# MinieasySens-RS485_V01-Build009.net
KiCad netlist of a schematic drawn in EAGLE
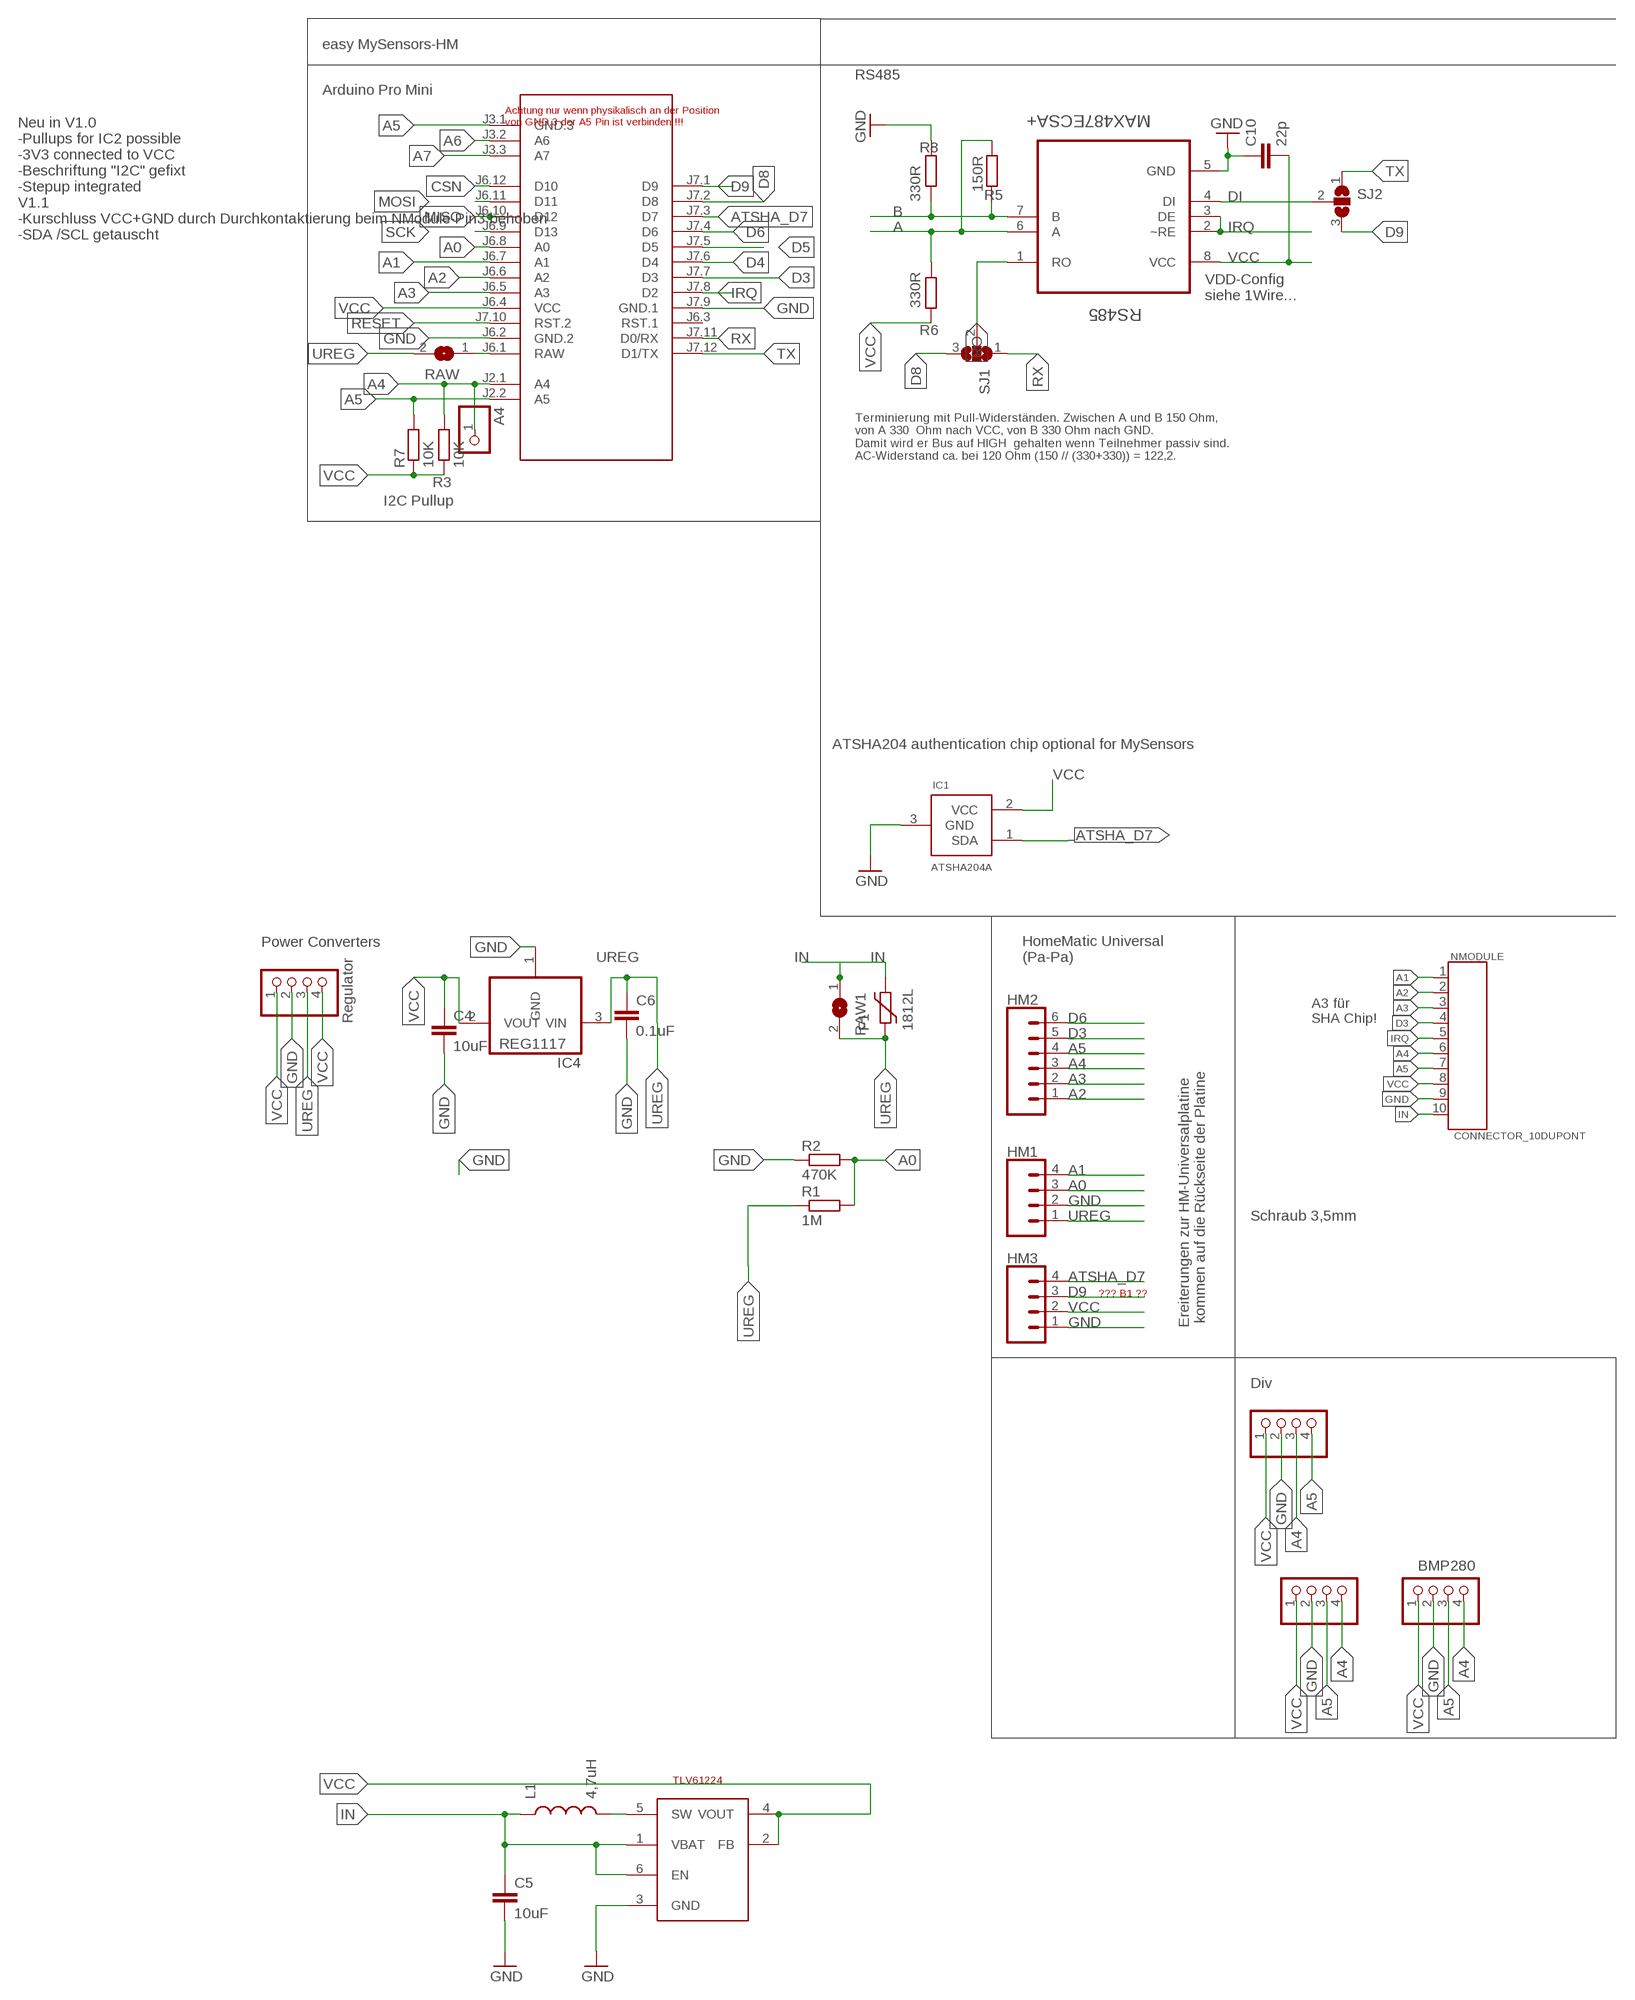
[diagram p0: schematic, sheet 1, part 1 of 2]
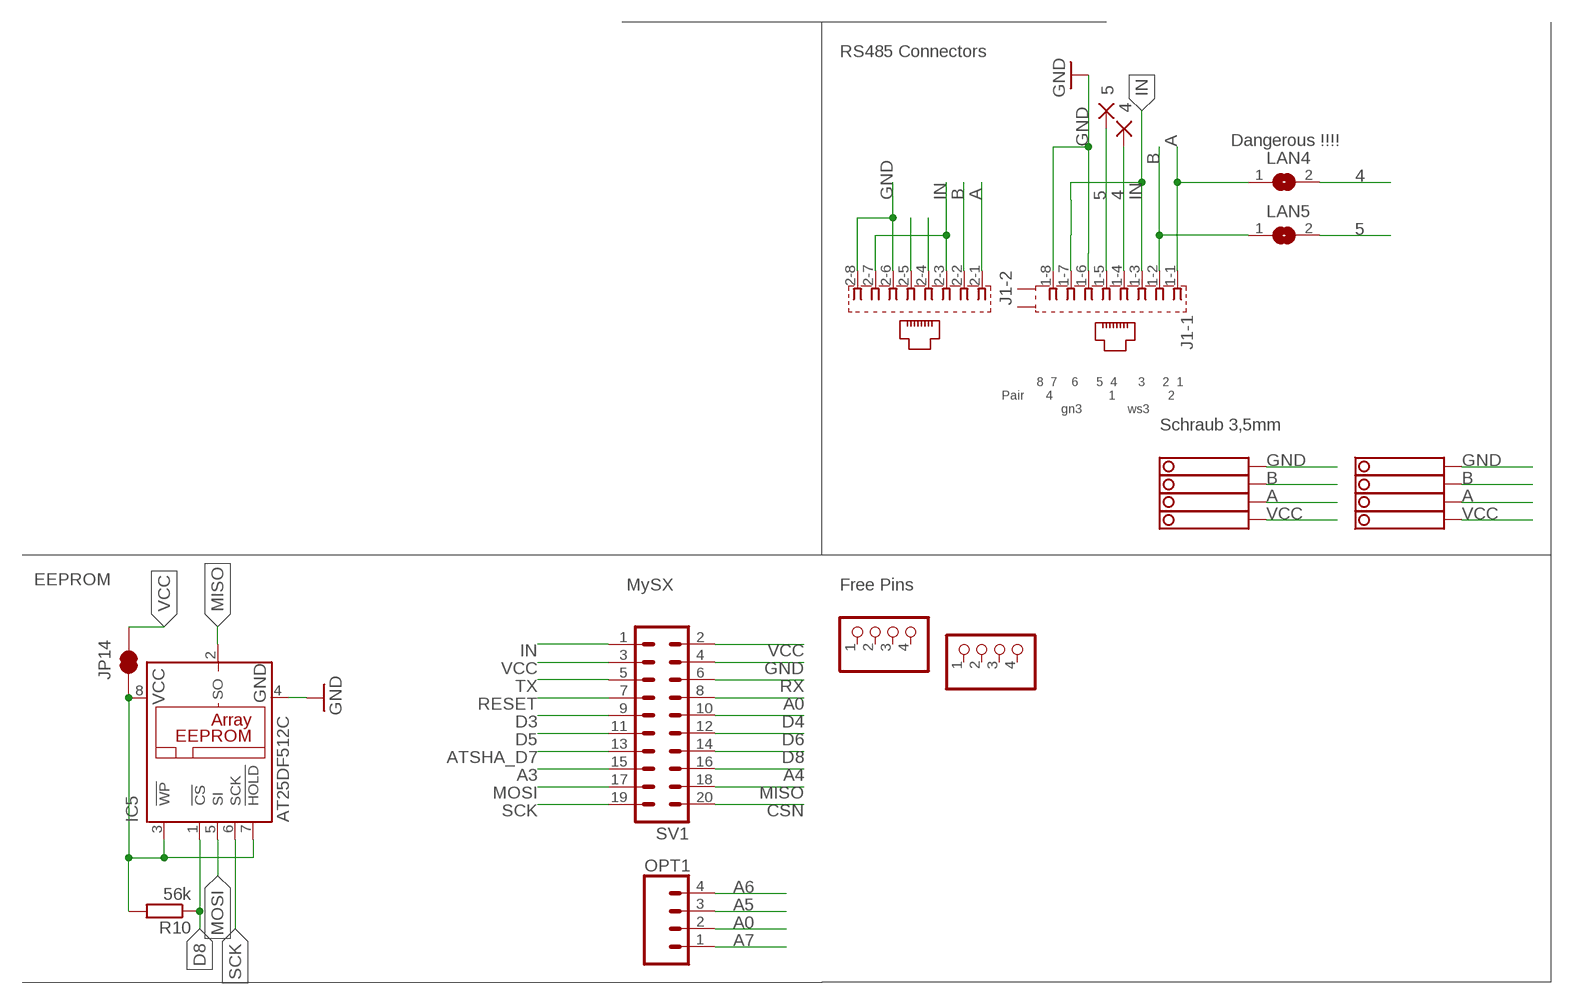
[diagram p1: schematic, sheet 1, part 2 of 2]

(export (version "E")
  (design (tool "Eeschema 10.0.6"))
  (components
    (comp (ref "4")
      (value "1,6/0,8")
      (footprint "eagle-import:1,6_0,8")
      (libsource (lib "eagle-import") (part "1,6/0,8"))
    )
    (comp (ref "5")
      (value "1,6/0,8")
      (footprint "eagle-import:1,6_0,8")
      (libsource (lib "eagle-import") (part "1,6/0,8"))
    )
    (comp (ref "A4")
      (value "PINHD-1X1")
      (footprint "eagle-import:1X01")
      (libsource (lib "eagle-import") (part "PINHD-1X1"))
    )
    (comp (ref "BH1750")
      (value "PINHD-1X04_2.54-S")
      (footprint "eagle-import:1X04-S")
      (libsource (lib "eagle-import") (part "PINHD-1X04_2.54-S"))
    )
    (comp (ref "C4")
      (value "10uF")
      (footprint "eagle-import:C1210")
      (libsource (lib "eagle-import") (part "C-EUC1210"))
    )
    (comp (ref "C5")
      (value "10uF")
      (footprint "eagle-import:0805")
      (libsource (lib "eagle-import") (part "CAP0805"))
    )
    (comp (ref "C6")
      (value "0.1uF")
      (footprint "eagle-import:C1206")
      (libsource (lib "eagle-import") (part "C-EUC1206"))
    )
    (comp (ref "C10")
      (value "22p")
      (footprint "eagle-import:C0805")
      (libsource (lib "eagle-import") (part "C-EUC0805"))
    )
    (comp (ref "F1")
      (value "1812L")
      (footprint "eagle-import:1812L")
      (libsource (lib "eagle-import") (part "1812L"))
    )
    (comp (ref "HM1")
      (value "CONN_04")
      (footprint "eagle-import:1X04")
      (libsource (lib "eagle-import") (part "CONN_04"))
    )
    (comp (ref "HM2")
      (value "CONN_06SILK_FEMALE_PTH")
      (footprint "eagle-import:1X06")
      (libsource (lib "eagle-import") (part "CONN_06SILK_FEMALE_PTH"))
    )
    (comp (ref "HM3")
      (value "CONN_04")
      (footprint "eagle-import:1X04")
      (libsource (lib "eagle-import") (part "CONN_04"))
    )
    (comp (ref "I2C-1")
      (value "PINHD-1X04_2.54-S")
      (footprint "eagle-import:1X04-S")
      (libsource (lib "eagle-import") (part "PINHD-1X04_2.54-S"))
    )
    (comp (ref "I2C-2")
      (value "PINHD-1X04_2.54-S")
      (footprint "eagle-import:1X04-S")
      (libsource (lib "eagle-import") (part "PINHD-1X04_2.54-S"))
    )
    (comp (ref "IC1")
      (value "ATSHA204A")
      (footprint "eagle-import:SOT23")
      (libsource (lib "eagle-import") (part "ATSHA204A"))
    )
    (comp (ref "IC4")
      (value "REG1117")
      (footprint "eagle-import:SOT223")
      (libsource (lib "eagle-import") (part "REG1117"))
    )
    (comp (ref "IC5")
      (value "AT25DF512C")
      (footprint "eagle-import:SO-08")
      (fields (field (name "MF") "MICROCHIP") (field (name "MPN") "25AA080/SN"))
      (libsource (lib "eagle-import") (part "25SNAA080"))
    )
    (comp (ref "J1")
      (value "557570-1")
      (footprint "eagle-import:557570-1")
      (libsource (lib "eagle-import") (part "557570-1"))
    )
    (comp (ref "JP2")
      (value "PINHD-1X04_2.54-S")
      (footprint "eagle-import:1X04-S")
      (libsource (lib "eagle-import") (part "PINHD-1X04_2.54-S"))
    )
    (comp (ref "JP4")
      (value "PINHD-1X04_2.54-S")
      (footprint "eagle-import:1X04-S")
      (libsource (lib "eagle-import") (part "PINHD-1X04_2.54-S"))
    )
    (comp (ref "JP14")
      (value "JUMPER-SMT_2_NC_TRACE_SILK")
      (footprint "eagle-import:SMT-JUMPER_2_NC_TRACE_SILK")
      (libsource (lib "eagle-import") (part "JUMPER-SMT_2_NC_TRACE_SILK"))
    )
    (comp (ref "L1")
      (value "4,7uH")
      (footprint "eagle-import:0805")
      (libsource (lib "eagle-import") (part "INDUCTOR0805"))
    )
    (comp (ref "LAN4")
      (value "SJ")
      (footprint "eagle-import:SJ")
      (libsource (lib "eagle-import") (part "SJ"))
    )
    (comp (ref "LAN5")
      (value "SJ")
      (footprint "eagle-import:SJ")
      (libsource (lib "eagle-import") (part "SJ"))
    )
    (comp (ref "M1")
      (value "ARDUINO-PRO-MINI-3.3V#NP")
      (footprint "eagle-import:ARDUINO-PRO-MINI#NP")
      (libsource (lib "eagle-import") (part "ARDUINO-PRO-MINI-#NP3.3V"))
    )
    (comp (ref "NMODULE")
      (value "CONNECTOR_10DUPONT")
      (footprint "eagle-import:DUPONT_10")
      (libsource (lib "eagle-import") (part "CONNECTOR_10DUPONT"))
    )
    (comp (ref "OPT1")
      (value "CONN_04")
      (footprint "eagle-import:1X04")
      (libsource (lib "eagle-import") (part "CONN_04"))
    )
    (comp (ref "R1")
      (value "1M")
      (footprint "eagle-import:R0805")
      (libsource (lib "eagle-import") (part "R-EU_R0805"))
    )
    (comp (ref "R2")
      (value "470K")
      (footprint "eagle-import:R0805")
      (libsource (lib "eagle-import") (part "R-EU_R0805"))
    )
    (comp (ref "R3")
      (value "10K")
      (footprint "eagle-import:R0805")
      (libsource (lib "eagle-import") (part "R-EU_R0805"))
    )
    (comp (ref "R5")
      (value "150R")
      (footprint "eagle-import:R0805")
      (libsource (lib "eagle-import") (part "R-EU_R0805"))
    )
    (comp (ref "R6")
      (value "330R")
      (footprint "eagle-import:R0805")
      (libsource (lib "eagle-import") (part "R-EU_R0805"))
    )
    (comp (ref "R7")
      (value "10K")
      (footprint "eagle-import:R0805")
      (libsource (lib "eagle-import") (part "R-EU_R0805"))
    )
    (comp (ref "R8")
      (value "330R")
      (footprint "eagle-import:R0805")
      (libsource (lib "eagle-import") (part "R-EU_R0805"))
    )
    (comp (ref "R10")
      (value "56k")
      (footprint "eagle-import:M0805")
      (libsource (lib "eagle-import") (part "resistor_R-EU_M0805"))
    )
    (comp (ref "RAW") (value "SJ") (footprint "eagle-import:SJ") (libsource (lib "eagle-import") (part "SJ")))
    (comp (ref "RAW1")
      (value "SJ")
      (footprint "eagle-import:SJ")
      (libsource (lib "eagle-import") (part "SJ"))
    )
    (comp (ref "RS485")
      (value "MAX487ECSA+")
      (footprint "eagle-import:SOIC127P600X175-8N")
      (libsource (lib "eagle-import") (part "MAX487ECSA+"))
    )
    (comp (ref "SJ1")
      (value "SJ2W")
      (footprint "eagle-import:SJ_2")
      (libsource (lib "eagle-import") (part "SJ2W"))
    )
    (comp (ref "SJ2")
      (value "SJ2W")
      (footprint "eagle-import:SJ_2")
      (libsource (lib "eagle-import") (part "SJ2W"))
    )
    (comp (ref "STEPDWN")
      (value "PINHD-1X04_2.54-S")
      (footprint "eagle-import:1X04-S")
      (libsource (lib "eagle-import") (part "PINHD-1X04_2.54-S"))
    )
    (comp (ref "STEPUP")
      (value "TLV61224")
      (footprint "eagle-import:SOT23-6L")
      (libsource (lib "eagle-import") (part "TI-TLV61224"))
    )
    (comp (ref "SV1")
      (value "MA10-2")
      (footprint "eagle-import:MA10-2")
      (libsource (lib "eagle-import") (part "MA10-2"))
    )
    (comp (ref "X1")
      (value "1751264")
      (footprint "eagle-import:1751264")
      (libsource (lib "eagle-import") (part "1751264"))
    )
    (comp (ref "X4")
      (value "1751264")
      (footprint "eagle-import:1751264")
      (libsource (lib "eagle-import") (part "1751264"))
    )
  )
  (nets
    (net (code "1") (name "/4") (class "Default")
      (node (ref "4") (pin "1") (pinfunction "P_1") (pintype "passive"))
      (node (ref "J1") (pin "1-4") (pinfunction "4_1-4") (pintype "passive"))
      (node (ref "LAN4") (pin "2") (pinfunction "2_2") (pintype "passive"))
    )
    (net (code "2") (name "/5") (class "Default")
      (node (ref "5") (pin "1") (pinfunction "P_1") (pintype "passive"))
      (node (ref "J1") (pin "1-5") (pinfunction "5_1-5") (pintype "passive"))
      (node (ref "LAN5") (pin "2") (pinfunction "2_2") (pintype "passive"))
    )
    (net (code "3") (name "/A") (class "Default")
      (node (ref "J1") (pin "1-1") (pinfunction "1_1-1") (pintype "passive"))
      (node (ref "J1") (pin "2-1") (pinfunction "1_2-1") (pintype "passive"))
      (node (ref "LAN4") (pin "1") (pinfunction "1_1") (pintype "passive"))
      (node (ref "R5") (pin "1") (pinfunction "1_1") (pintype "passive"))
      (node (ref "R6") (pin "2") (pinfunction "2_2") (pintype "passive"))
      (node (ref "RS485") (pin "6") (pinfunction "A_6") (pintype "bidirectional"))
      (node (ref "X1") (pin "2") (pinfunction "K_2") (pintype "passive"))
      (node (ref "X4") (pin "2") (pinfunction "K_2") (pintype "passive"))
    )
    (net (code "4") (name "/B") (class "Default")
      (node (ref "J1") (pin "1-2") (pinfunction "2_1-2") (pintype "passive"))
      (node (ref "J1") (pin "2-2") (pinfunction "2_2-2") (pintype "passive"))
      (node (ref "LAN5") (pin "1") (pinfunction "1_1") (pintype "passive"))
      (node (ref "R5") (pin "2") (pinfunction "2_2") (pintype "passive"))
      (node (ref "R8") (pin "1") (pinfunction "1_1") (pintype "passive"))
      (node (ref "RS485") (pin "7") (pinfunction "B_7") (pintype "bidirectional"))
      (node (ref "X1") (pin "3") (pinfunction "K_3") (pintype "passive"))
      (node (ref "X4") (pin "3") (pinfunction "K_3") (pintype "passive"))
    )
    (net (code "5") (name "/DI") (class "Default")
      (node (ref "RS485") (pin "4") (pinfunction "DI_4") (pintype "input"))
      (node (ref "SJ2") (pin "2") (pinfunction "2_2") (pintype "passive"))
    )
    (net (code "6") (name "A0") (class "Default")
      (node (ref "HM1") (pin "3") (pinfunction "3_3") (pintype "passive"))
      (node (ref "M1") (pin "J6.8") (pinfunction "A0_J6.8") (pintype "bidirectional"))
      (node (ref "OPT1") (pin "2") (pinfunction "2_2") (pintype "passive"))
      (node (ref "R1") (pin "2") (pinfunction "2_2") (pintype "passive"))
      (node (ref "R2") (pin "2") (pinfunction "2_2") (pintype "passive"))
      (node (ref "SV1") (pin "8") (pinfunction "8_8") (pintype "passive"))
    )
    (net (code "7") (name "A1") (class "Default")
      (node (ref "HM1") (pin "4") (pinfunction "4_4") (pintype "passive"))
      (node (ref "M1") (pin "J6.7") (pinfunction "A1_J6.7") (pintype "bidirectional"))
      (node (ref "NMODULE") (pin "1") (pinfunction "1_1") (pintype "bidirectional"))
    )
    (net (code "8") (name "A2") (class "Default")
      (node (ref "HM2") (pin "1") (pinfunction "1_1") (pintype "passive"))
      (node (ref "M1") (pin "J6.6") (pinfunction "A2_J6.6") (pintype "bidirectional"))
      (node (ref "NMODULE") (pin "2") (pinfunction "2_2") (pintype "bidirectional"))
    )
    (net (code "9") (name "A3") (class "Default")
      (node (ref "HM2") (pin "2") (pinfunction "2_2") (pintype "passive"))
      (node (ref "M1") (pin "J6.5") (pinfunction "A3_J6.5") (pintype "bidirectional"))
      (node (ref "NMODULE") (pin "3") (pinfunction "3_3") (pintype "bidirectional"))
      (node (ref "SV1") (pin "15") (pinfunction "15_15") (pintype "passive"))
    )
    (net (code "10") (name "A4") (class "Default")
      (node (ref "A4") (pin "1") (pinfunction "1_1") (pintype "passive"))
      (node (ref "BH1750") (pin "4") (pinfunction "4_4") (pintype "passive"))
      (node (ref "HM2") (pin "3") (pinfunction "3_3") (pintype "passive"))
      (node (ref "I2C-1") (pin "4") (pinfunction "4_4") (pintype "passive"))
      (node (ref "I2C-2") (pin "3") (pinfunction "3_3") (pintype "passive"))
      (node (ref "M1") (pin "J2.1") (pinfunction "A4_J2.1") (pintype "bidirectional"))
      (node (ref "NMODULE") (pin "6") (pinfunction "6_6") (pintype "bidirectional"))
      (node (ref "R3") (pin "2") (pinfunction "2_2") (pintype "passive"))
      (node (ref "SV1") (pin "16") (pinfunction "16_16") (pintype "passive"))
    )
    (net (code "11") (name "A5") (class "Default")
      (node (ref "BH1750") (pin "3") (pinfunction "3_3") (pintype "passive"))
      (node (ref "HM2") (pin "4") (pinfunction "4_4") (pintype "passive"))
      (node (ref "I2C-1") (pin "3") (pinfunction "3_3") (pintype "passive"))
      (node (ref "I2C-2") (pin "4") (pinfunction "4_4") (pintype "passive"))
      (node (ref "M1") (pin "J2.2") (pinfunction "A5_J2.2") (pintype "bidirectional"))
      (node (ref "M1") (pin "J3.1") (pinfunction "GND.3_J3.1") (pintype "bidirectional"))
      (node (ref "NMODULE") (pin "7") (pinfunction "7_7") (pintype "bidirectional"))
      (node (ref "OPT1") (pin "3") (pinfunction "3_3") (pintype "passive"))
      (node (ref "R7") (pin "2") (pinfunction "2_2") (pintype "passive"))
    )
    (net (code "12") (name "A6") (class "Default")
      (node (ref "M1") (pin "J3.2") (pinfunction "A6_J3.2") (pintype "bidirectional"))
      (node (ref "OPT1") (pin "4") (pinfunction "4_4") (pintype "passive"))
    )
    (net (code "13") (name "A7") (class "Default")
      (node (ref "M1") (pin "J3.3") (pinfunction "A7_J3.3") (pintype "bidirectional"))
      (node (ref "OPT1") (pin "1") (pinfunction "1_1") (pintype "passive"))
    )
    (net (code "14") (name "ATSHA_D7") (class "Default")
      (node (ref "HM3") (pin "4") (pinfunction "4_4") (pintype "passive"))
      (node (ref "IC1") (pin "1") (pinfunction "SDA_1") (pintype "bidirectional"))
      (node (ref "M1") (pin "J7.3") (pinfunction "D7_J7.3") (pintype "bidirectional"))
      (node (ref "SV1") (pin "13") (pinfunction "13_13") (pintype "passive"))
    )
    (net (code "15") (name "CSN") (class "Default")
      (node (ref "M1") (pin "J6.12") (pinfunction "D10_J6.12") (pintype "bidirectional"))
      (node (ref "SV1") (pin "20") (pinfunction "20_20") (pintype "passive"))
    )
    (net (code "16") (name "D3") (class "Default")
      (node (ref "HM2") (pin "5") (pinfunction "5_5") (pintype "passive"))
      (node (ref "M1") (pin "J7.7") (pinfunction "D3_J7.7") (pintype "bidirectional"))
      (node (ref "NMODULE") (pin "4") (pinfunction "4_4") (pintype "bidirectional"))
      (node (ref "SV1") (pin "9") (pinfunction "9_9") (pintype "passive"))
    )
    (net (code "17") (name "D4") (class "Default")
      (node (ref "M1") (pin "J7.6") (pinfunction "D4_J7.6") (pintype "bidirectional"))
      (node (ref "SV1") (pin "10") (pinfunction "10_10") (pintype "passive"))
    )
    (net (code "18") (name "D5") (class "Default")
      (node (ref "M1") (pin "J7.5") (pinfunction "D5_J7.5") (pintype "bidirectional"))
      (node (ref "SV1") (pin "11") (pinfunction "11_11") (pintype "passive"))
    )
    (net (code "19") (name "D6") (class "Default")
      (node (ref "HM2") (pin "6") (pinfunction "6_6") (pintype "passive"))
      (node (ref "M1") (pin "J7.4") (pinfunction "D6_J7.4") (pintype "bidirectional"))
      (node (ref "SV1") (pin "12") (pinfunction "12_12") (pintype "passive"))
    )
    (net (code "20") (name "D8") (class "Default")
      (node (ref "IC5") (pin "1") (pinfunction "~{CS}_1") (pintype "input"))
      (node (ref "M1") (pin "J7.2") (pinfunction "D8_J7.2") (pintype "bidirectional"))
      (node (ref "R10") (pin "1") (pinfunction "1_1") (pintype "passive"))
      (node (ref "SJ1") (pin "3") (pinfunction "3_3") (pintype "passive"))
      (node (ref "SV1") (pin "14") (pinfunction "14_14") (pintype "passive"))
    )
    (net (code "21") (name "D9") (class "Default")
      (node (ref "HM3") (pin "3") (pinfunction "3_3") (pintype "passive"))
      (node (ref "M1") (pin "J7.1") (pinfunction "D9_J7.1") (pintype "bidirectional"))
      (node (ref "SJ2") (pin "3") (pinfunction "3_3") (pintype "passive"))
    )
    (net (code "22") (name "GND") (class "Default")
      (node (ref "BH1750") (pin "2") (pinfunction "2_2") (pintype "passive"))
      (node (ref "C10") (pin "1") (pinfunction "1_1") (pintype "passive"))
      (node (ref "C4") (pin "2") (pinfunction "2_2") (pintype "passive"))
      (node (ref "C5") (pin "2") (pinfunction "2_2") (pintype "passive"))
      (node (ref "C6") (pin "2") (pinfunction "2_2") (pintype "passive"))
      (node (ref "HM1") (pin "2") (pinfunction "2_2") (pintype "passive"))
      (node (ref "HM3") (pin "1") (pinfunction "1_1") (pintype "passive"))
      (node (ref "I2C-1") (pin "2") (pinfunction "2_2") (pintype "passive"))
      (node (ref "I2C-2") (pin "2") (pinfunction "2_2") (pintype "passive"))
      (node (ref "IC1") (pin "3") (pinfunction "GND_3") (pintype "bidirectional"))
      (node (ref "IC4") (pin "1") (pinfunction "GND_1") (pintype "power_in"))
      (node (ref "IC5") (pin "4") (pinfunction "GND_4") (pintype "power_in"))
      (node (ref "J1") (pin "1-6") (pinfunction "6_1-6") (pintype "passive"))
      (node (ref "J1") (pin "1-8") (pinfunction "8_1-8") (pintype "passive"))
      (node (ref "J1") (pin "2-6") (pinfunction "6_2-6") (pintype "passive"))
      (node (ref "J1") (pin "2-8") (pinfunction "8_2-8") (pintype "passive"))
      (node (ref "M1") (pin "J6.2") (pinfunction "GND.2_J6.2") (pintype "power_in"))
      (node (ref "M1") (pin "J7.9") (pinfunction "GND.1_J7.9") (pintype "power_in"))
      (node (ref "NMODULE") (pin "9") (pinfunction "9_9") (pintype "bidirectional"))
      (node (ref "R2") (pin "1") (pinfunction "1_1") (pintype "passive"))
      (node (ref "R8") (pin "2") (pinfunction "2_2") (pintype "passive"))
      (node (ref "RS485") (pin "5") (pinfunction "GND_5") (pintype "passive"))
      (node (ref "STEPDWN") (pin "2") (pinfunction "2_2") (pintype "passive"))
      (node (ref "STEPUP") (pin "3") (pinfunction "GND_3") (pintype "power_in"))
      (node (ref "SV1") (pin "4") (pinfunction "4_4") (pintype "passive"))
      (node (ref "X1") (pin "4") (pinfunction "K_4") (pintype "passive"))
      (node (ref "X4") (pin "4") (pinfunction "K_4") (pintype "passive"))
    )
    (net (code "23") (name "IN") (class "Default")
      (node (ref "C5") (pin "1") (pinfunction "1_1") (pintype "passive"))
      (node (ref "F1") (pin "P$2") (pinfunction "2_P$2") (pintype "passive"))
      (node (ref "J1") (pin "1-3") (pinfunction "3_1-3") (pintype "passive"))
      (node (ref "J1") (pin "1-7") (pinfunction "7_1-7") (pintype "passive"))
      (node (ref "J1") (pin "2-3") (pinfunction "3_2-3") (pintype "passive"))
      (node (ref "J1") (pin "2-7") (pinfunction "7_2-7") (pintype "passive"))
      (node (ref "L1") (pin "1") (pinfunction "1_1") (pintype "passive"))
      (node (ref "NMODULE") (pin "10") (pinfunction "10_10") (pintype "bidirectional"))
      (node (ref "RAW1") (pin "1") (pinfunction "1_1") (pintype "passive"))
      (node (ref "STEPUP") (pin "1") (pinfunction "VBAT_1") (pintype "power_in"))
      (node (ref "STEPUP") (pin "6") (pinfunction "EN_6") (pintype "input"))
      (node (ref "SV1") (pin "1") (pinfunction "1_1") (pintype "passive"))
    )
    (net (code "24") (name "IRQ") (class "Default")
      (node (ref "M1") (pin "J7.8") (pinfunction "D2_J7.8") (pintype "bidirectional"))
      (node (ref "NMODULE") (pin "5") (pinfunction "5_5") (pintype "bidirectional"))
      (node (ref "RS485") (pin "2") (pinfunction "~{RE}_2") (pintype "input"))
      (node (ref "RS485") (pin "3") (pinfunction "DE_3") (pintype "input"))
    )
    (net (code "25") (name "MISO") (class "Default")
      (node (ref "IC5") (pin "2") (pinfunction "SO_2") (pintype "bidirectional"))
      (node (ref "M1") (pin "J6.10") (pinfunction "D12_J6.10") (pintype "bidirectional"))
      (node (ref "SV1") (pin "18") (pinfunction "18_18") (pintype "passive"))
    )
    (net (code "26") (name "MOSI") (class "Default")
      (node (ref "IC5") (pin "5") (pinfunction "SI_5") (pintype "input"))
      (node (ref "M1") (pin "J6.11") (pinfunction "D11_J6.11") (pintype "bidirectional"))
      (node (ref "SV1") (pin "17") (pinfunction "17_17") (pintype "passive"))
    )
    (net (code "27") (name "Net-(IC5-VCC)") (class "Default")
      (node (ref "IC5") (pin "3") (pinfunction "~{WP}_3") (pintype "input"))
      (node (ref "IC5") (pin "7") (pinfunction "~{HOLD}_7") (pintype "input"))
      (node (ref "IC5") (pin "8") (pinfunction "VCC_8") (pintype "power_in"))
      (node (ref "JP14") (pin "1") (pinfunction "1_1") (pintype "passive"))
      (node (ref "R10") (pin "2") (pinfunction "2_2") (pintype "passive"))
    )
    (net (code "28") (name "Net-(M1-RAW)") (class "Default")
      (node (ref "M1") (pin "J6.1") (pinfunction "RAW_J6.1") (pintype "power_in"))
      (node (ref "RAW") (pin "1") (pinfunction "1_1") (pintype "passive"))
    )
    (net (code "29") (name "Net-(STEPUP-SW)") (class "Default")
      (node (ref "L1") (pin "2") (pinfunction "2_2") (pintype "passive"))
      (node (ref "STEPUP") (pin "5") (pinfunction "SW_5") (pintype "power_in"))
    )
    (net (code "30") (name "RESET") (class "Default")
      (node (ref "M1") (pin "J7.10") (pinfunction "RST.2_J7.10") (pintype "bidirectional"))
      (node (ref "SV1") (pin "7") (pinfunction "7_7") (pintype "passive"))
    )
    (net (code "31") (name "RO") (class "Default")
      (node (ref "RS485") (pin "1") (pinfunction "RO_1") (pintype "output"))
      (node (ref "SJ1") (pin "2") (pinfunction "2_2") (pintype "passive"))
    )
    (net (code "32") (name "RX") (class "Default")
      (node (ref "M1") (pin "J7.11") (pinfunction "D0/RX_J7.11") (pintype "bidirectional"))
      (node (ref "SJ1") (pin "1") (pinfunction "1_1") (pintype "passive"))
      (node (ref "SV1") (pin "6") (pinfunction "6_6") (pintype "passive"))
    )
    (net (code "33") (name "SCK") (class "Default")
      (node (ref "IC5") (pin "6") (pinfunction "SCK_6") (pintype "input"))
      (node (ref "M1") (pin "J6.9") (pinfunction "D13_J6.9") (pintype "bidirectional"))
      (node (ref "SV1") (pin "19") (pinfunction "19_19") (pintype "passive"))
    )
    (net (code "34") (name "TX") (class "Default")
      (node (ref "M1") (pin "J7.12") (pinfunction "D1/TX_J7.12") (pintype "bidirectional"))
      (node (ref "SJ2") (pin "1") (pinfunction "1_1") (pintype "passive"))
      (node (ref "SV1") (pin "5") (pinfunction "5_5") (pintype "passive"))
    )
    (net (code "35") (name "UREG") (class "Default")
      (node (ref "C6") (pin "1") (pinfunction "1_1") (pintype "passive"))
      (node (ref "F1") (pin "P$1") (pinfunction "1_P$1") (pintype "passive"))
      (node (ref "HM1") (pin "1") (pinfunction "1_1") (pintype "passive"))
      (node (ref "IC4") (pin "3") (pinfunction "VIN_3") (pintype "input"))
      (node (ref "R1") (pin "1") (pinfunction "1_1") (pintype "passive"))
      (node (ref "RAW") (pin "2") (pinfunction "2_2") (pintype "passive"))
      (node (ref "RAW1") (pin "2") (pinfunction "2_2") (pintype "passive"))
      (node (ref "STEPDWN") (pin "3") (pinfunction "3_3") (pintype "passive"))
    )
    (net (code "36") (name "VCC") (class "Default")
      (node (ref "BH1750") (pin "1") (pinfunction "1_1") (pintype "passive"))
      (node (ref "C10") (pin "2") (pinfunction "2_2") (pintype "passive"))
      (node (ref "C4") (pin "1") (pinfunction "1_1") (pintype "passive"))
      (node (ref "HM3") (pin "2") (pinfunction "2_2") (pintype "passive"))
      (node (ref "I2C-1") (pin "1") (pinfunction "1_1") (pintype "passive"))
      (node (ref "I2C-2") (pin "1") (pinfunction "1_1") (pintype "passive"))
      (node (ref "IC1") (pin "2") (pinfunction "VCC_2") (pintype "bidirectional"))
      (node (ref "IC4") (pin "2") (pinfunction "VOUT_2") (pintype "output"))
      (node (ref "JP14") (pin "2") (pinfunction "2_2") (pintype "passive"))
      (node (ref "M1") (pin "J6.4") (pinfunction "VCC_J6.4") (pintype "power_in"))
      (node (ref "NMODULE") (pin "8") (pinfunction "8_8") (pintype "bidirectional"))
      (node (ref "R3") (pin "1") (pinfunction "1_1") (pintype "passive"))
      (node (ref "R6") (pin "1") (pinfunction "1_1") (pintype "passive"))
      (node (ref "R7") (pin "1") (pinfunction "1_1") (pintype "passive"))
      (node (ref "RS485") (pin "8") (pinfunction "VCC_8") (pintype "power_in"))
      (node (ref "STEPDWN") (pin "1") (pinfunction "1_1") (pintype "passive"))
      (node (ref "STEPDWN") (pin "4") (pinfunction "4_4") (pintype "passive"))
      (node (ref "STEPUP") (pin "2") (pinfunction "FB_2") (pintype "input"))
      (node (ref "STEPUP") (pin "4") (pinfunction "VOUT_4") (pintype "power_in"))
      (node (ref "SV1") (pin "2") (pinfunction "2_2") (pintype "passive"))
      (node (ref "SV1") (pin "3") (pinfunction "3_3") (pintype "passive"))
      (node (ref "X1") (pin "1") (pinfunction "K_1") (pintype "passive"))
      (node (ref "X4") (pin "1") (pinfunction "K_1") (pintype "passive"))
    )
    (net (code "37") (name "unconnected-(J1A-S1-PadG3)") (class "Default")
      (node (ref "J1") (pin "G3") (pinfunction "S1_G3") (pintype "passive"))
    )
    (net (code "38") (name "unconnected-(J1A-S2-PadG1)") (class "Default")
      (node (ref "J1") (pin "G1") (pinfunction "S2_G1") (pintype "passive"))
    )
    (net (code "39") (name "unconnected-(J1B-4-Pad2-4)") (class "Default")
      (node (ref "J1") (pin "2-4") (pinfunction "4_2-4") (pintype "passive"))
    )
    (net (code "40") (name "unconnected-(J1B-5-Pad2-5)") (class "Default")
      (node (ref "J1") (pin "2-5") (pinfunction "5_2-5") (pintype "passive"))
    )
    (net (code "41") (name "unconnected-(JP2-Pad1)") (class "Default")
      (node (ref "JP2") (pin "1") (pinfunction "1_1") (pintype "passive"))
    )
    (net (code "42") (name "unconnected-(JP2-Pad2)") (class "Default")
      (node (ref "JP2") (pin "2") (pinfunction "2_2") (pintype "passive"))
    )
    (net (code "43") (name "unconnected-(JP2-Pad3)") (class "Default")
      (node (ref "JP2") (pin "3") (pinfunction "3_3") (pintype "passive"))
    )
    (net (code "44") (name "unconnected-(JP2-Pad4)") (class "Default")
      (node (ref "JP2") (pin "4") (pinfunction "4_4") (pintype "passive"))
    )
    (net (code "45") (name "unconnected-(JP4-Pad1)") (class "Default")
      (node (ref "JP4") (pin "1") (pinfunction "1_1") (pintype "passive"))
    )
    (net (code "46") (name "unconnected-(JP4-Pad2)") (class "Default")
      (node (ref "JP4") (pin "2") (pinfunction "2_2") (pintype "passive"))
    )
    (net (code "47") (name "unconnected-(JP4-Pad3)") (class "Default")
      (node (ref "JP4") (pin "3") (pinfunction "3_3") (pintype "passive"))
    )
    (net (code "48") (name "unconnected-(JP4-Pad4)") (class "Default")
      (node (ref "JP4") (pin "4") (pinfunction "4_4") (pintype "passive"))
    )
    (net (code "49") (name "unconnected-(M1-RST.1-PadJ6.3)") (class "Default")
      (node (ref "M1") (pin "J6.3") (pinfunction "RST.1_J6.3") (pintype "bidirectional"))
    )
  )
)
